# bot_power_supply_pcb.net
KiCad netlist of a schematic drawn in EAGLE
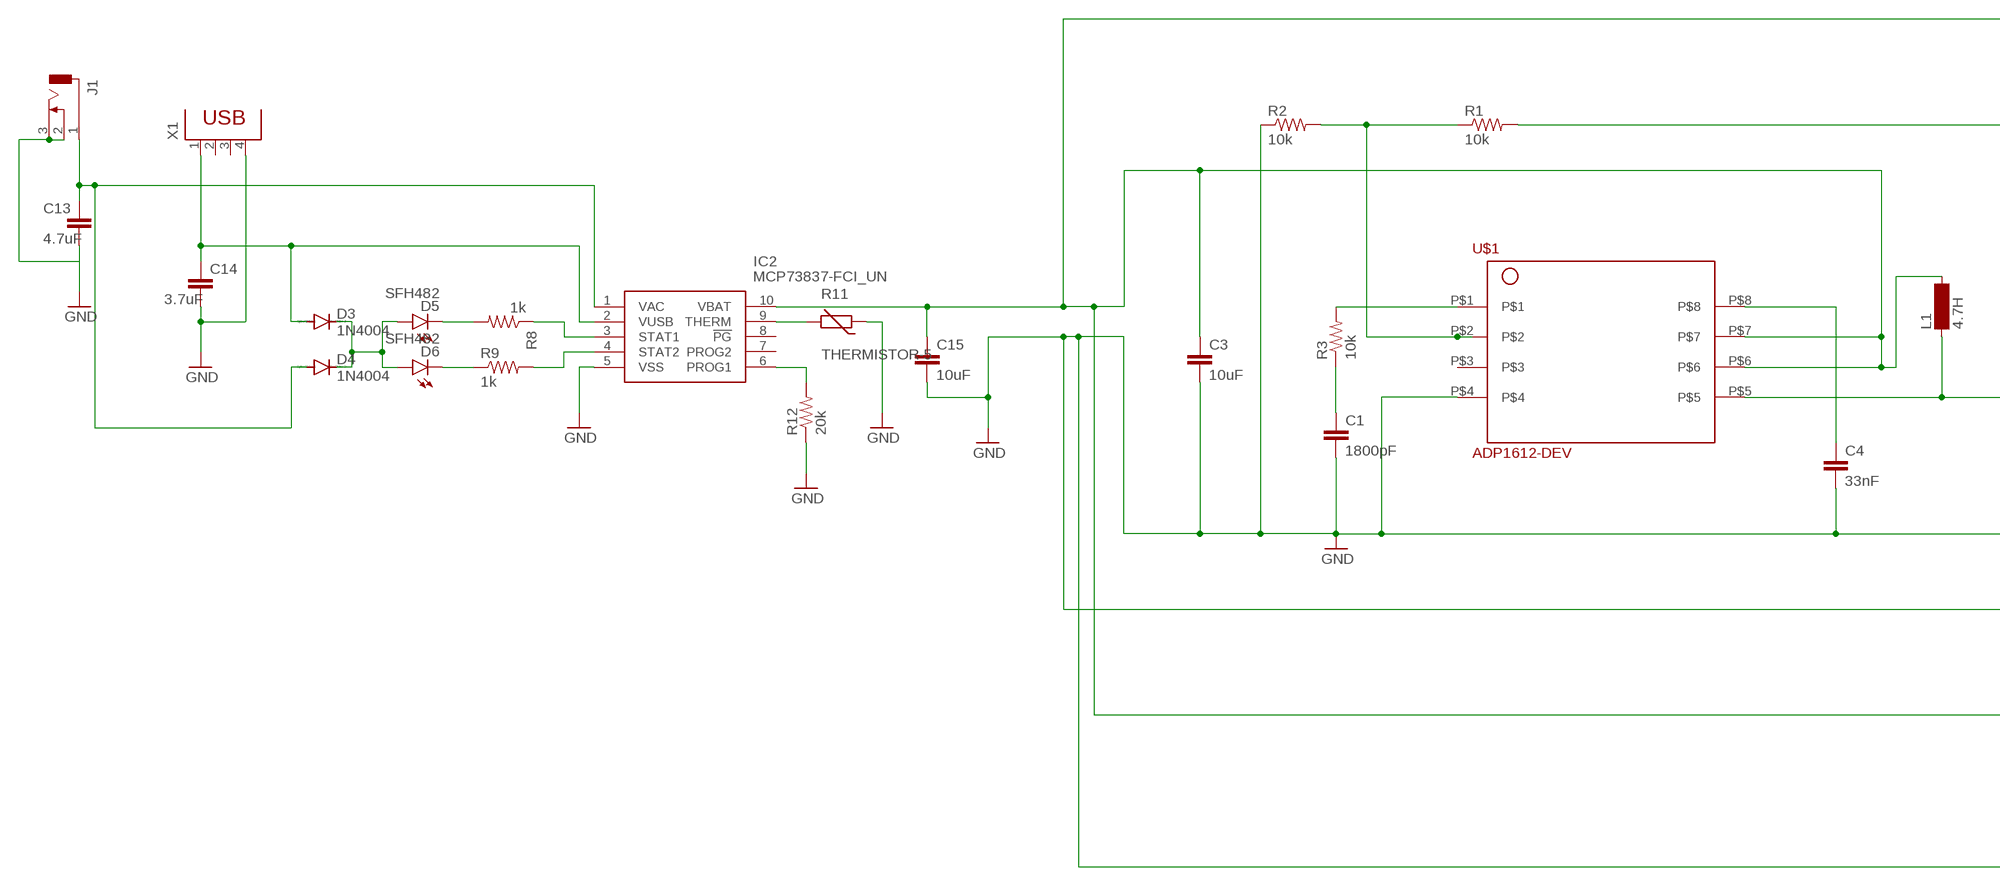
[diagram p0: schematic, sheet 1, part 1 of 2]
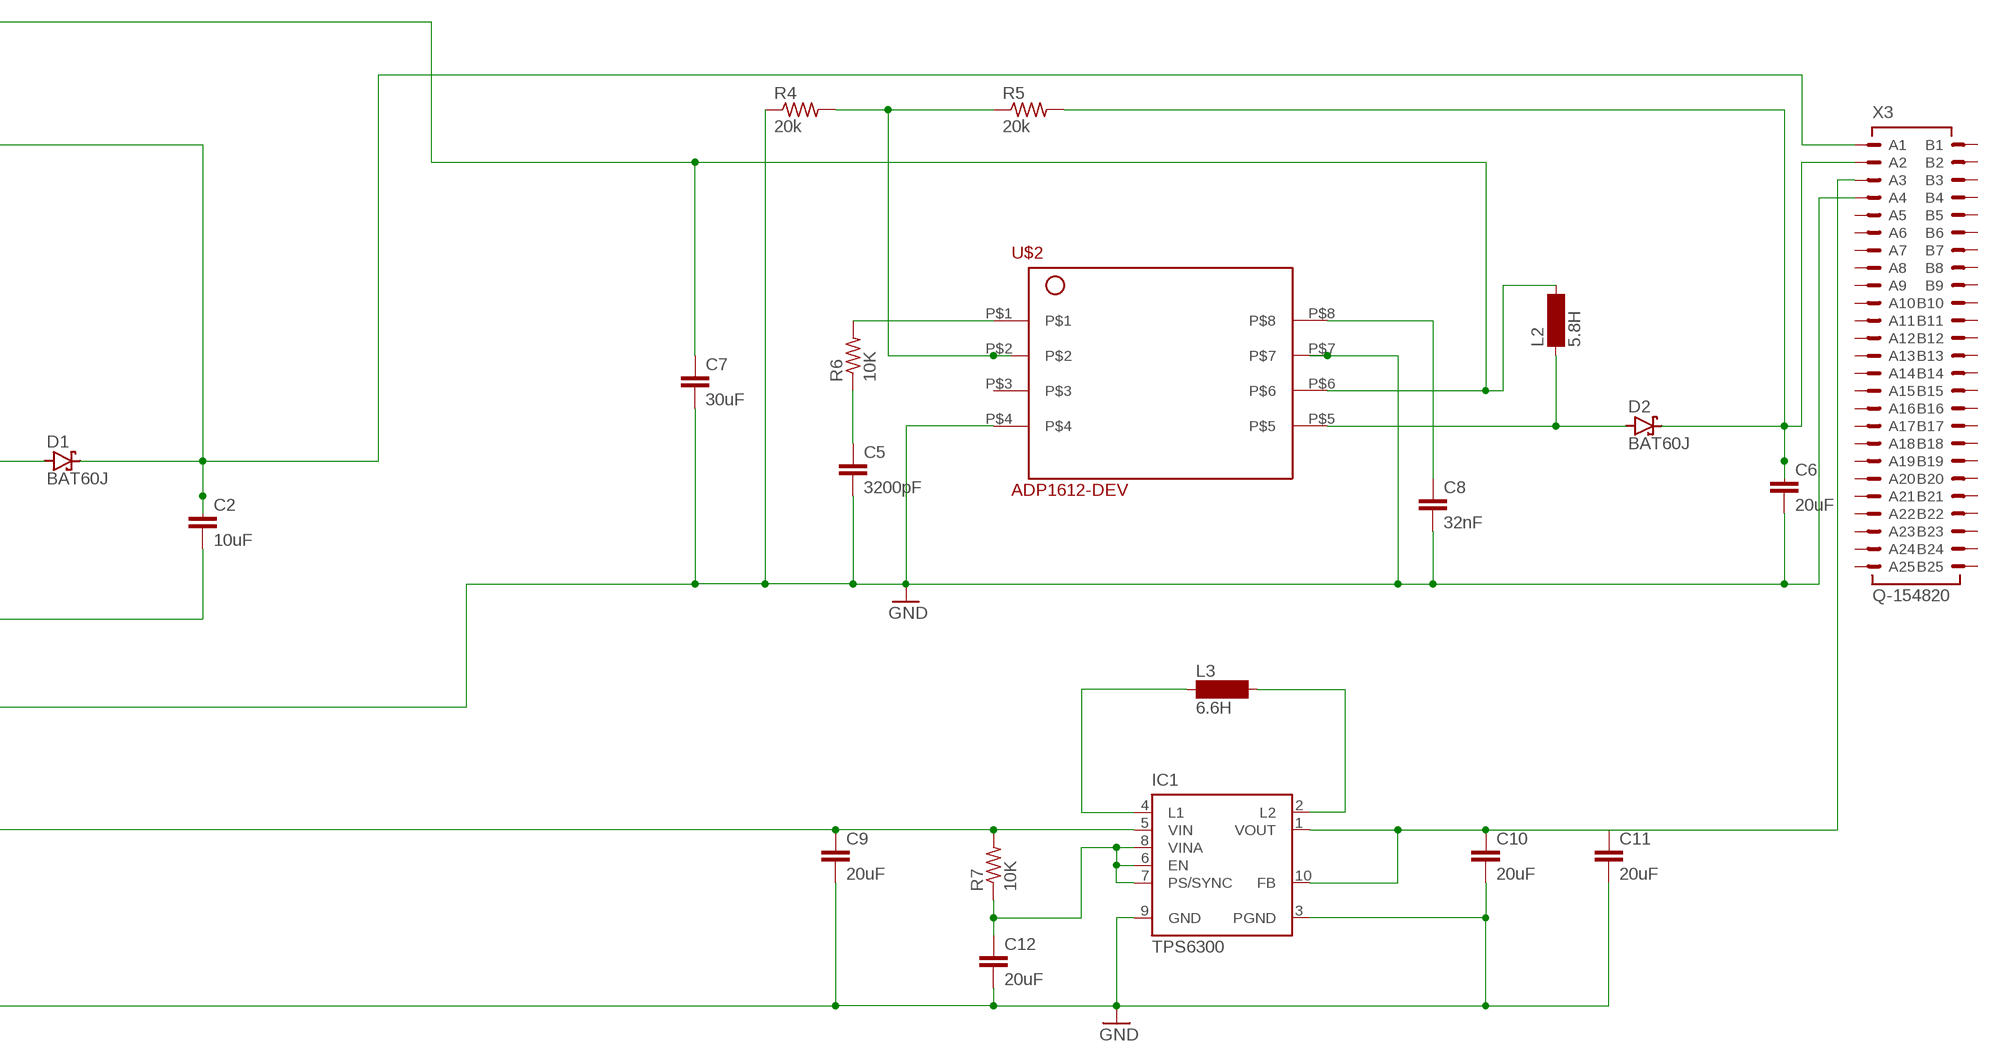
[diagram p1: schematic, sheet 1, part 2 of 2]

(export (version "E")
  (design (tool "Eeschema 10.0.6"))
  (components
    (comp (ref "C1")
      (value "1800pF")
      (footprint "eagle-import:C2.5-4")
      (libsource (lib "eagle-import") (part "C2.5/4"))
    )
    (comp (ref "C2")
      (value "10uF")
      (footprint "eagle-import:C2.5-4")
      (libsource (lib "eagle-import") (part "C2.5/4"))
    )
    (comp (ref "C3")
      (value "10uF")
      (footprint "eagle-import:C2.5-4")
      (libsource (lib "eagle-import") (part "C2.5/4"))
    )
    (comp (ref "C4")
      (value "33nF")
      (footprint "eagle-import:C2.5-4")
      (libsource (lib "eagle-import") (part "C2.5/4"))
    )
    (comp (ref "C5")
      (value "3200pF")
      (footprint "eagle-import:C2.5-4")
      (libsource (lib "eagle-import") (part "C2.5/4"))
    )
    (comp (ref "C6")
      (value "20uF")
      (footprint "eagle-import:C2.5-4")
      (libsource (lib "eagle-import") (part "C2.5/4"))
    )
    (comp (ref "C7")
      (value "30uF")
      (footprint "eagle-import:C2.5-4")
      (libsource (lib "eagle-import") (part "C2.5/4"))
    )
    (comp (ref "C8")
      (value "32nF")
      (footprint "eagle-import:C2.5-4")
      (libsource (lib "eagle-import") (part "C2.5/4"))
    )
    (comp (ref "C9")
      (value "20uF")
      (footprint "eagle-import:C2.5-3")
      (libsource (lib "eagle-import") (part "C2,5-3"))
    )
    (comp (ref "C10")
      (value "20uF")
      (footprint "eagle-import:C2.5-3")
      (libsource (lib "eagle-import") (part "C2,5-3"))
    )
    (comp (ref "C11")
      (value "20uF")
      (footprint "eagle-import:C2.5-3")
      (libsource (lib "eagle-import") (part "C2,5-3"))
    )
    (comp (ref "C12")
      (value "20uF")
      (footprint "eagle-import:C2.5-3")
      (libsource (lib "eagle-import") (part "C2,5-3"))
    )
    (comp (ref "C13")
      (value "4.7uF")
      (footprint "eagle-import:C2.5-3")
      (libsource (lib "eagle-import") (part "C2,5-3"))
    )
    (comp (ref "C14")
      (value "3.7uF")
      (footprint "eagle-import:C2.5-3")
      (libsource (lib "eagle-import") (part "C2,5-3"))
    )
    (comp (ref "C15")
      (value "10uF")
      (footprint "eagle-import:C2.5-3")
      (libsource (lib "eagle-import") (part "C2,5-3"))
    )
    (comp (ref "D1")
      (value "BAT60J")
      (footprint "eagle-import:SOD323_ST")
      (libsource (lib "eagle-import") (part "BAT60J"))
    )
    (comp (ref "D2")
      (value "BAT60J")
      (footprint "eagle-import:SOD323_ST")
      (libsource (lib "eagle-import") (part "BAT60J"))
    )
    (comp (ref "D3")
      (value "1N4004")
      (footprint "eagle-import:DO41-10")
      (libsource (lib "eagle-import") (part "1N4004"))
    )
    (comp (ref "D4")
      (value "1N4004")
      (footprint "eagle-import:DO41-10")
      (libsource (lib "eagle-import") (part "1N4004"))
    )
    (comp (ref "D5")
      (value "SFH482")
      (footprint "eagle-import:SFH482")
      (libsource (lib "eagle-import") (part "SFH482"))
    )
    (comp (ref "D6")
      (value "SFH482")
      (footprint "eagle-import:SFH482")
      (libsource (lib "eagle-import") (part "SFH482"))
    )
    (comp (ref "IC1")
      (value "TPS6300")
      (footprint "eagle-import:DRC-S-PVSON-N10")
      (fields (field (name "MPN") "TPS63000DRCTG4"))
      (libsource (lib "eagle-import") (part "TPS6300"))
    )
    (comp (ref "IC2")
      (value "MCP73837-FCI_UN")
      (footprint "eagle-import:SOP50P490X110-10N")
      (fields
        (field (name "ARROW_PART_NUMBER") "MCP73837-FCI/UN")
        (field (name "MOUSER_PART_NUMBER") "579-MCP73837-FCI/UN")
      )
      (libsource (lib "eagle-import") (part "MCP73837-FCI_UN"))
    )
    (comp (ref "J1")
      (value "DCJ0303")
      (footprint "eagle-import:DCJ0303")
      (libsource (lib "eagle-import") (part "DCJ0303"))
    )
    (comp (ref "L1")
      (value "4.7H")
      (footprint "eagle-import:BS11")
      (libsource (lib "eagle-import") (part "BS11"))
    )
    (comp (ref "L2")
      (value "5.8H")
      (footprint "eagle-import:BS11")
      (libsource (lib "eagle-import") (part "BS11"))
    )
    (comp (ref "L3")
      (value "6.6H")
      (footprint "eagle-import:BS75")
      (libsource (lib "eagle-import") (part "BS75"))
    )
    (comp (ref "R1")
      (value "10k")
      (footprint "eagle-import:0204_7")
      (libsource (lib "eagle-import") (part "R-US_0204/7"))
    )
    (comp (ref "R2")
      (value "10k")
      (footprint "eagle-import:0204_7")
      (libsource (lib "eagle-import") (part "R-US_0204/7"))
    )
    (comp (ref "R3")
      (value "10k")
      (footprint "eagle-import:0204_7")
      (libsource (lib "eagle-import") (part "R-US_0204/7"))
    )
    (comp (ref "R4")
      (value "20k")
      (footprint "eagle-import:0204_7")
      (libsource (lib "eagle-import") (part "R-US_0204/7"))
    )
    (comp (ref "R5")
      (value "20k")
      (footprint "eagle-import:0204_7")
      (libsource (lib "eagle-import") (part "R-US_0204/7"))
    )
    (comp (ref "R6")
      (value "10K")
      (footprint "eagle-import:0204_7")
      (libsource (lib "eagle-import") (part "R-US_0204/7"))
    )
    (comp (ref "R7")
      (value "10K")
      (footprint "eagle-import:0204_5")
      (libsource (lib "eagle-import") (part "R-US_0204/5"))
    )
    (comp (ref "R8")
      (value "1k")
      (footprint "eagle-import:0204_5")
      (libsource (lib "eagle-import") (part "R-US_0204/5"))
    )
    (comp (ref "R9")
      (value "1k")
      (footprint "eagle-import:0204_5")
      (libsource (lib "eagle-import") (part "R-US_0204/5"))
    )
    (comp (ref "R11")
      (value "THERMISTOR-5")
      (footprint "eagle-import:R-5")
      (libsource (lib "eagle-import") (part "THERMISTOR-5"))
    )
    (comp (ref "R12")
      (value "20k")
      (footprint "eagle-import:0204_5")
      (libsource (lib "eagle-import") (part "R-US_0204/5"))
    )
    (comp (ref "U$1")
      (value "ADP1612-DEV")
      (footprint "eagle-import:TQFP-ADP1612")
      (libsource (lib "eagle-import") (part "ADP1612-DEV"))
    )
    (comp (ref "U$2")
      (value "ADP1612-DEV")
      (footprint "eagle-import:TQFP-ADP1612")
      (libsource (lib "eagle-import") (part "ADP1612-DEV"))
    )
    (comp (ref "X1")
      (value "PN61729")
      (footprint "eagle-import:PN61729")
      (libsource (lib "eagle-import") (part "PN61729"))
    )
    (comp (ref "X3")
      (value "Q-154820")
      (footprint "eagle-import:154820")
      (libsource (lib "eagle-import") (part "Q-154820"))
    )
  )
  (nets
    (net (code "1") (name "GND") (class "Default")
      (node (ref "C1") (pin "2") (pinfunction "2_2") (pintype "passive"))
      (node (ref "C10") (pin "2") (pinfunction "2_2") (pintype "passive"))
      (node (ref "C11") (pin "2") (pinfunction "2_2") (pintype "passive"))
      (node (ref "C12") (pin "2") (pinfunction "2_2") (pintype "passive"))
      (node (ref "C13") (pin "2") (pinfunction "2_2") (pintype "passive"))
      (node (ref "C14") (pin "1") (pinfunction "1_1") (pintype "passive"))
      (node (ref "C14") (pin "2") (pinfunction "2_2") (pintype "passive"))
      (node (ref "C15") (pin "2") (pinfunction "2_2") (pintype "passive"))
      (node (ref "C2") (pin "2") (pinfunction "2_2") (pintype "passive"))
      (node (ref "C3") (pin "2") (pinfunction "2_2") (pintype "passive"))
      (node (ref "C4") (pin "2") (pinfunction "2_2") (pintype "passive"))
      (node (ref "C5") (pin "2") (pinfunction "2_2") (pintype "passive"))
      (node (ref "C6") (pin "2") (pinfunction "2_2") (pintype "passive"))
      (node (ref "C7") (pin "2") (pinfunction "2_2") (pintype "passive"))
      (node (ref "C8") (pin "2") (pinfunction "2_2") (pintype "passive"))
      (node (ref "C9") (pin "2") (pinfunction "2_2") (pintype "passive"))
      (node (ref "D3") (pin "A") (pinfunction "A_A") (pintype "passive"))
      (node (ref "IC1") (pin "3") (pinfunction "PGND_3") (pintype "power_in"))
      (node (ref "IC1") (pin "9") (pinfunction "GND_9") (pintype "power_in"))
      (node (ref "IC2") (pin "2") (pinfunction "VUSB_2") (pintype "bidirectional"))
      (node (ref "IC2") (pin "5") (pinfunction "VSS_5") (pintype "power_in"))
      (node (ref "J1") (pin "2") (pinfunction "2_2") (pintype "passive"))
      (node (ref "J1") (pin "3") (pinfunction "3_3") (pintype "passive"))
      (node (ref "R11") (pin "1") (pinfunction "1_1") (pintype "passive"))
      (node (ref "R12") (pin "1") (pinfunction "1_1") (pintype "passive"))
      (node (ref "R2") (pin "1") (pinfunction "1_1") (pintype "passive"))
      (node (ref "R4") (pin "1") (pinfunction "1_1") (pintype "passive"))
      (node (ref "U$1") (pin "P$4") (pinfunction "P$4_P$4") (pintype "bidirectional"))
      (node (ref "U$2") (pin "P$4") (pinfunction "P$4_P$4") (pintype "bidirectional"))
      (node (ref "U$2") (pin "P$7") (pinfunction "P$7_P$7") (pintype "bidirectional"))
      (node (ref "X1") (pin "1") (pinfunction "1_1") (pintype "passive"))
      (node (ref "X1") (pin "4") (pinfunction "4_4") (pintype "passive"))
      (node (ref "X3") (pin "A4") (pinfunction "A4_A4") (pintype "passive"))
    )
    (net (code "2") (name "Net-(C1-Pad1)") (class "Default")
      (node (ref "C1") (pin "1") (pinfunction "1_1") (pintype "passive"))
      (node (ref "R3") (pin "1") (pinfunction "1_1") (pintype "passive"))
    )
    (net (code "3") (name "Net-(C2-Pad1)") (class "Default")
      (node (ref "C2") (pin "1") (pinfunction "1_1") (pintype "passive"))
      (node (ref "D1") (pin "C") (pinfunction "C_C") (pintype "passive"))
      (node (ref "R1") (pin "2") (pinfunction "2_2") (pintype "passive"))
      (node (ref "X3") (pin "A1") (pinfunction "A1_A1") (pintype "passive"))
    )
    (net (code "4") (name "Net-(C4-Pad1)") (class "Default")
      (node (ref "C4") (pin "1") (pinfunction "1_1") (pintype "passive"))
      (node (ref "U$1") (pin "P$8") (pinfunction "P$8_P$8") (pintype "bidirectional"))
    )
    (net (code "5") (name "Net-(C5-Pad1)") (class "Default")
      (node (ref "C5") (pin "1") (pinfunction "1_1") (pintype "passive"))
      (node (ref "R6") (pin "1") (pinfunction "1_1") (pintype "passive"))
    )
    (net (code "6") (name "Net-(C6-Pad1)") (class "Default")
      (node (ref "C6") (pin "1") (pinfunction "1_1") (pintype "passive"))
      (node (ref "D2") (pin "C") (pinfunction "C_C") (pintype "passive"))
      (node (ref "R5") (pin "2") (pinfunction "2_2") (pintype "passive"))
      (node (ref "X3") (pin "A2") (pinfunction "A2_A2") (pintype "passive"))
    )
    (net (code "7") (name "Net-(C8-Pad1)") (class "Default")
      (node (ref "C8") (pin "1") (pinfunction "1_1") (pintype "passive"))
      (node (ref "U$2") (pin "P$8") (pinfunction "P$8_P$8") (pintype "bidirectional"))
    )
    (net (code "8") (name "Net-(D1-PadA)") (class "Default")
      (node (ref "D1") (pin "A") (pinfunction "A_A") (pintype "passive"))
      (node (ref "L1") (pin "1") (pinfunction "1_1") (pintype "passive"))
      (node (ref "U$1") (pin "P$5") (pinfunction "P$5_P$5") (pintype "bidirectional"))
    )
    (net (code "9") (name "Net-(D2-PadA)") (class "Default")
      (node (ref "D2") (pin "A") (pinfunction "A_A") (pintype "passive"))
      (node (ref "L2") (pin "1") (pinfunction "1_1") (pintype "passive"))
      (node (ref "U$2") (pin "P$5") (pinfunction "P$5_P$5") (pintype "bidirectional"))
    )
    (net (code "10") (name "Net-(D3-PadC)") (class "Default")
      (node (ref "D3") (pin "C") (pinfunction "C_C") (pintype "passive"))
      (node (ref "D4") (pin "C") (pinfunction "C_C") (pintype "passive"))
      (node (ref "D5") (pin "A") (pinfunction "A_A") (pintype "passive"))
      (node (ref "D6") (pin "A") (pinfunction "A_A") (pintype "passive"))
    )
    (net (code "11") (name "Net-(D5-C)") (class "Default")
      (node (ref "D5") (pin "K") (pinfunction "C_K") (pintype "passive"))
      (node (ref "R8") (pin "2") (pinfunction "2_2") (pintype "passive"))
    )
    (net (code "12") (name "Net-(D6-C)") (class "Default")
      (node (ref "D6") (pin "K") (pinfunction "C_K") (pintype "passive"))
      (node (ref "R9") (pin "1") (pinfunction "1_1") (pintype "passive"))
    )
    (net (code "13") (name "Net-(IC1A-EN)") (class "Default")
      (node (ref "C12") (pin "1") (pinfunction "1_1") (pintype "passive"))
      (node (ref "IC1") (pin "6") (pinfunction "EN_6") (pintype "input"))
      (node (ref "IC1") (pin "7") (pinfunction "PS/SYNC_7") (pintype "input"))
      (node (ref "IC1") (pin "8") (pinfunction "VINA_8") (pintype "input"))
      (node (ref "R7") (pin "1") (pinfunction "1_1") (pintype "passive"))
    )
    (net (code "14") (name "Net-(IC1A-FB)") (class "Default")
      (node (ref "C10") (pin "1") (pinfunction "1_1") (pintype "passive"))
      (node (ref "C11") (pin "1") (pinfunction "1_1") (pintype "passive"))
      (node (ref "IC1") (pin "1") (pinfunction "VOUT_1") (pintype "output"))
      (node (ref "IC1") (pin "10") (pinfunction "FB_10") (pintype "input"))
      (node (ref "X3") (pin "A3") (pinfunction "A3_A3") (pintype "passive"))
    )
    (net (code "15") (name "Net-(IC1A-L1)") (class "Default")
      (node (ref "IC1") (pin "4") (pinfunction "L1_4") (pintype "passive"))
      (node (ref "L3") (pin "1") (pinfunction "1_1") (pintype "passive"))
    )
    (net (code "16") (name "Net-(IC1A-L2)") (class "Default")
      (node (ref "IC1") (pin "2") (pinfunction "L2_2") (pintype "passive"))
      (node (ref "L3") (pin "2") (pinfunction "2_2") (pintype "passive"))
    )
    (net (code "17") (name "Net-(IC1A-VIN)") (class "Default")
      (node (ref "C15") (pin "1") (pinfunction "1_1") (pintype "passive"))
      (node (ref "C3") (pin "1") (pinfunction "1_1") (pintype "passive"))
      (node (ref "C7") (pin "1") (pinfunction "1_1") (pintype "passive"))
      (node (ref "C9") (pin "1") (pinfunction "1_1") (pintype "passive"))
      (node (ref "IC1") (pin "5") (pinfunction "VIN_5") (pintype "input"))
      (node (ref "IC2") (pin "10") (pinfunction "VBAT_10") (pintype "bidirectional"))
      (node (ref "L1") (pin "2") (pinfunction "2_2") (pintype "passive"))
      (node (ref "L2") (pin "2") (pinfunction "2_2") (pintype "passive"))
      (node (ref "R7") (pin "2") (pinfunction "2_2") (pintype "passive"))
      (node (ref "U$1") (pin "P$6") (pinfunction "P$6_P$6") (pintype "bidirectional"))
      (node (ref "U$1") (pin "P$7") (pinfunction "P$7_P$7") (pintype "bidirectional"))
      (node (ref "U$2") (pin "P$6") (pinfunction "P$6_P$6") (pintype "bidirectional"))
    )
    (net (code "18") (name "Net-(IC2-PROG1)") (class "Default")
      (node (ref "IC2") (pin "6") (pinfunction "PROG1_6") (pintype "bidirectional"))
      (node (ref "R12") (pin "2") (pinfunction "2_2") (pintype "passive"))
    )
    (net (code "19") (name "Net-(IC2-STAT1)") (class "Default")
      (node (ref "IC2") (pin "3") (pinfunction "STAT1_3") (pintype "bidirectional"))
      (node (ref "R8") (pin "1") (pinfunction "1_1") (pintype "passive"))
    )
    (net (code "20") (name "Net-(IC2-STAT2)") (class "Default")
      (node (ref "IC2") (pin "4") (pinfunction "STAT2_4") (pintype "bidirectional"))
      (node (ref "R9") (pin "2") (pinfunction "2_2") (pintype "passive"))
    )
    (net (code "21") (name "Net-(IC2-THERM)") (class "Default")
      (node (ref "IC2") (pin "9") (pinfunction "THERM_9") (pintype "bidirectional"))
      (node (ref "R11") (pin "2") (pinfunction "2_2") (pintype "passive"))
    )
    (net (code "22") (name "Net-(IC2-VAC)") (class "Default")
      (node (ref "C13") (pin "1") (pinfunction "1_1") (pintype "passive"))
      (node (ref "D4") (pin "A") (pinfunction "A_A") (pintype "passive"))
      (node (ref "IC2") (pin "1") (pinfunction "VAC_1") (pintype "bidirectional"))
      (node (ref "J1") (pin "1") (pinfunction "1_1") (pintype "passive"))
    )
    (net (code "23") (name "Net-(R1-Pad1)") (class "Default")
      (node (ref "R1") (pin "1") (pinfunction "1_1") (pintype "passive"))
      (node (ref "R2") (pin "2") (pinfunction "2_2") (pintype "passive"))
      (node (ref "U$1") (pin "P$2") (pinfunction "P$2_P$2") (pintype "bidirectional"))
    )
    (net (code "24") (name "Net-(R3-Pad2)") (class "Default")
      (node (ref "R3") (pin "2") (pinfunction "2_2") (pintype "passive"))
      (node (ref "U$1") (pin "P$1") (pinfunction "P$1_P$1") (pintype "bidirectional"))
    )
    (net (code "25") (name "Net-(R4-Pad2)") (class "Default")
      (node (ref "R4") (pin "2") (pinfunction "2_2") (pintype "passive"))
      (node (ref "R5") (pin "1") (pinfunction "1_1") (pintype "passive"))
      (node (ref "U$2") (pin "P$2") (pinfunction "P$2_P$2") (pintype "bidirectional"))
    )
    (net (code "26") (name "Net-(R6-Pad2)") (class "Default")
      (node (ref "R6") (pin "2") (pinfunction "2_2") (pintype "passive"))
      (node (ref "U$2") (pin "P$1") (pinfunction "P$1_P$1") (pintype "bidirectional"))
    )
    (net (code "27") (name "unconnected-(IC2-PROG2-Pad7)") (class "Default")
      (node (ref "IC2") (pin "7") (pinfunction "PROG2_7") (pintype "bidirectional"))
    )
    (net (code "28") (name "unconnected-(IC2-~{PG}-Pad8)") (class "Default")
      (node (ref "IC2") (pin "8") (pinfunction "~{PG}_8") (pintype "bidirectional"))
    )
    (net (code "29") (name "unconnected-(U$1-PadP$3)") (class "Default")
      (node (ref "U$1") (pin "P$3") (pinfunction "P$3_P$3") (pintype "bidirectional"))
    )
    (net (code "30") (name "unconnected-(U$2-PadP$3)") (class "Default")
      (node (ref "U$2") (pin "P$3") (pinfunction "P$3_P$3") (pintype "bidirectional"))
    )
    (net (code "31") (name "unconnected-(X1-Pad2)") (class "Default")
      (node (ref "X1") (pin "2") (pinfunction "2_2") (pintype "passive"))
    )
    (net (code "32") (name "unconnected-(X1-Pad3)") (class "Default")
      (node (ref "X1") (pin "3") (pinfunction "3_3") (pintype "passive"))
    )
    (net (code "33") (name "unconnected-(X3-PadA5)") (class "Default")
      (node (ref "X3") (pin "A5") (pinfunction "A5_A5") (pintype "passive"))
    )
    (net (code "34") (name "unconnected-(X3-PadA6)") (class "Default")
      (node (ref "X3") (pin "A6") (pinfunction "A6_A6") (pintype "passive"))
    )
    (net (code "35") (name "unconnected-(X3-PadA7)") (class "Default")
      (node (ref "X3") (pin "A7") (pinfunction "A7_A7") (pintype "passive"))
    )
    (net (code "36") (name "unconnected-(X3-PadA8)") (class "Default")
      (node (ref "X3") (pin "A8") (pinfunction "A8_A8") (pintype "passive"))
    )
    (net (code "37") (name "unconnected-(X3-PadA9)") (class "Default")
      (node (ref "X3") (pin "A9") (pinfunction "A9_A9") (pintype "passive"))
    )
    (net (code "38") (name "unconnected-(X3-PadA10)") (class "Default")
      (node (ref "X3") (pin "A10") (pinfunction "A10_A10") (pintype "passive"))
    )
    (net (code "39") (name "unconnected-(X3-PadA11)") (class "Default")
      (node (ref "X3") (pin "A11") (pinfunction "A11_A11") (pintype "passive"))
    )
    (net (code "40") (name "unconnected-(X3-PadA12)") (class "Default")
      (node (ref "X3") (pin "A12") (pinfunction "A12_A12") (pintype "passive"))
    )
    (net (code "41") (name "unconnected-(X3-PadA13)") (class "Default")
      (node (ref "X3") (pin "A13") (pinfunction "A13_A13") (pintype "passive"))
    )
    (net (code "42") (name "unconnected-(X3-PadA14)") (class "Default")
      (node (ref "X3") (pin "A14") (pinfunction "A14_A14") (pintype "passive"))
    )
    (net (code "43") (name "unconnected-(X3-PadA15)") (class "Default")
      (node (ref "X3") (pin "A15") (pinfunction "A15_A15") (pintype "passive"))
    )
    (net (code "44") (name "unconnected-(X3-PadA16)") (class "Default")
      (node (ref "X3") (pin "A16") (pinfunction "A16_A16") (pintype "passive"))
    )
    (net (code "45") (name "unconnected-(X3-PadA17)") (class "Default")
      (node (ref "X3") (pin "A17") (pinfunction "A17_A17") (pintype "passive"))
    )
    (net (code "46") (name "unconnected-(X3-PadA18)") (class "Default")
      (node (ref "X3") (pin "A18") (pinfunction "A18_A18") (pintype "passive"))
    )
    (net (code "47") (name "unconnected-(X3-PadA19)") (class "Default")
      (node (ref "X3") (pin "A19") (pinfunction "A19_A19") (pintype "passive"))
    )
    (net (code "48") (name "unconnected-(X3-PadA20)") (class "Default")
      (node (ref "X3") (pin "A20") (pinfunction "A20_A20") (pintype "passive"))
    )
    (net (code "49") (name "unconnected-(X3-PadA21)") (class "Default")
      (node (ref "X3") (pin "A21") (pinfunction "A21_A21") (pintype "passive"))
    )
    (net (code "50") (name "unconnected-(X3-PadA22)") (class "Default")
      (node (ref "X3") (pin "A22") (pinfunction "A22_A22") (pintype "passive"))
    )
    (net (code "51") (name "unconnected-(X3-PadA23)") (class "Default")
      (node (ref "X3") (pin "A23") (pinfunction "A23_A23") (pintype "passive"))
    )
    (net (code "52") (name "unconnected-(X3-PadA24)") (class "Default")
      (node (ref "X3") (pin "A24") (pinfunction "A24_A24") (pintype "passive"))
    )
    (net (code "53") (name "unconnected-(X3-PadA25)") (class "Default")
      (node (ref "X3") (pin "A25") (pinfunction "A25_A25") (pintype "passive"))
    )
    (net (code "54") (name "unconnected-(X3-PadB1)") (class "Default")
      (node (ref "X3") (pin "B1") (pinfunction "B1_B1") (pintype "passive"))
    )
    (net (code "55") (name "unconnected-(X3-PadB2)") (class "Default")
      (node (ref "X3") (pin "B2") (pinfunction "B2_B2") (pintype "passive"))
    )
    (net (code "56") (name "unconnected-(X3-PadB3)") (class "Default")
      (node (ref "X3") (pin "B3") (pinfunction "B3_B3") (pintype "passive"))
    )
    (net (code "57") (name "unconnected-(X3-PadB4)") (class "Default")
      (node (ref "X3") (pin "B4") (pinfunction "B4_B4") (pintype "passive"))
    )
    (net (code "58") (name "unconnected-(X3-PadB5)") (class "Default")
      (node (ref "X3") (pin "B5") (pinfunction "B5_B5") (pintype "passive"))
    )
    (net (code "59") (name "unconnected-(X3-PadB6)") (class "Default")
      (node (ref "X3") (pin "B6") (pinfunction "B6_B6") (pintype "passive"))
    )
    (net (code "60") (name "unconnected-(X3-PadB7)") (class "Default")
      (node (ref "X3") (pin "B7") (pinfunction "B7_B7") (pintype "passive"))
    )
    (net (code "61") (name "unconnected-(X3-PadB8)") (class "Default")
      (node (ref "X3") (pin "B8") (pinfunction "B8_B8") (pintype "passive"))
    )
    (net (code "62") (name "unconnected-(X3-PadB9)") (class "Default")
      (node (ref "X3") (pin "B9") (pinfunction "B9_B9") (pintype "passive"))
    )
    (net (code "63") (name "unconnected-(X3-PadB10)") (class "Default")
      (node (ref "X3") (pin "B10") (pinfunction "B10_B10") (pintype "passive"))
    )
    (net (code "64") (name "unconnected-(X3-PadB11)") (class "Default")
      (node (ref "X3") (pin "B11") (pinfunction "B11_B11") (pintype "passive"))
    )
    (net (code "65") (name "unconnected-(X3-PadB12)") (class "Default")
      (node (ref "X3") (pin "B12") (pinfunction "B12_B12") (pintype "passive"))
    )
    (net (code "66") (name "unconnected-(X3-PadB13)") (class "Default")
      (node (ref "X3") (pin "B13") (pinfunction "B13_B13") (pintype "passive"))
    )
    (net (code "67") (name "unconnected-(X3-PadB14)") (class "Default")
      (node (ref "X3") (pin "B14") (pinfunction "B14_B14") (pintype "passive"))
    )
    (net (code "68") (name "unconnected-(X3-PadB15)") (class "Default")
      (node (ref "X3") (pin "B15") (pinfunction "B15_B15") (pintype "passive"))
    )
    (net (code "69") (name "unconnected-(X3-PadB16)") (class "Default")
      (node (ref "X3") (pin "B16") (pinfunction "B16_B16") (pintype "passive"))
    )
    (net (code "70") (name "unconnected-(X3-PadB17)") (class "Default")
      (node (ref "X3") (pin "B17") (pinfunction "B17_B17") (pintype "passive"))
    )
    (net (code "71") (name "unconnected-(X3-PadB18)") (class "Default")
      (node (ref "X3") (pin "B18") (pinfunction "B18_B18") (pintype "passive"))
    )
    (net (code "72") (name "unconnected-(X3-PadB19)") (class "Default")
      (node (ref "X3") (pin "B19") (pinfunction "B19_B19") (pintype "passive"))
    )
    (net (code "73") (name "unconnected-(X3-PadB20)") (class "Default")
      (node (ref "X3") (pin "B20") (pinfunction "B20_B20") (pintype "passive"))
    )
    (net (code "74") (name "unconnected-(X3-PadB21)") (class "Default")
      (node (ref "X3") (pin "B21") (pinfunction "B21_B21") (pintype "passive"))
    )
    (net (code "75") (name "unconnected-(X3-PadB22)") (class "Default")
      (node (ref "X3") (pin "B22") (pinfunction "B22_B22") (pintype "passive"))
    )
    (net (code "76") (name "unconnected-(X3-PadB23)") (class "Default")
      (node (ref "X3") (pin "B23") (pinfunction "B23_B23") (pintype "passive"))
    )
    (net (code "77") (name "unconnected-(X3-PadB24)") (class "Default")
      (node (ref "X3") (pin "B24") (pinfunction "B24_B24") (pintype "passive"))
    )
    (net (code "78") (name "unconnected-(X3-PadB25)") (class "Default")
      (node (ref "X3") (pin "B25") (pinfunction "B25_B25") (pintype "passive"))
    )
  )
)
